# stm32_pi_board.net
KiCad netlist of a schematic drawn in EAGLE
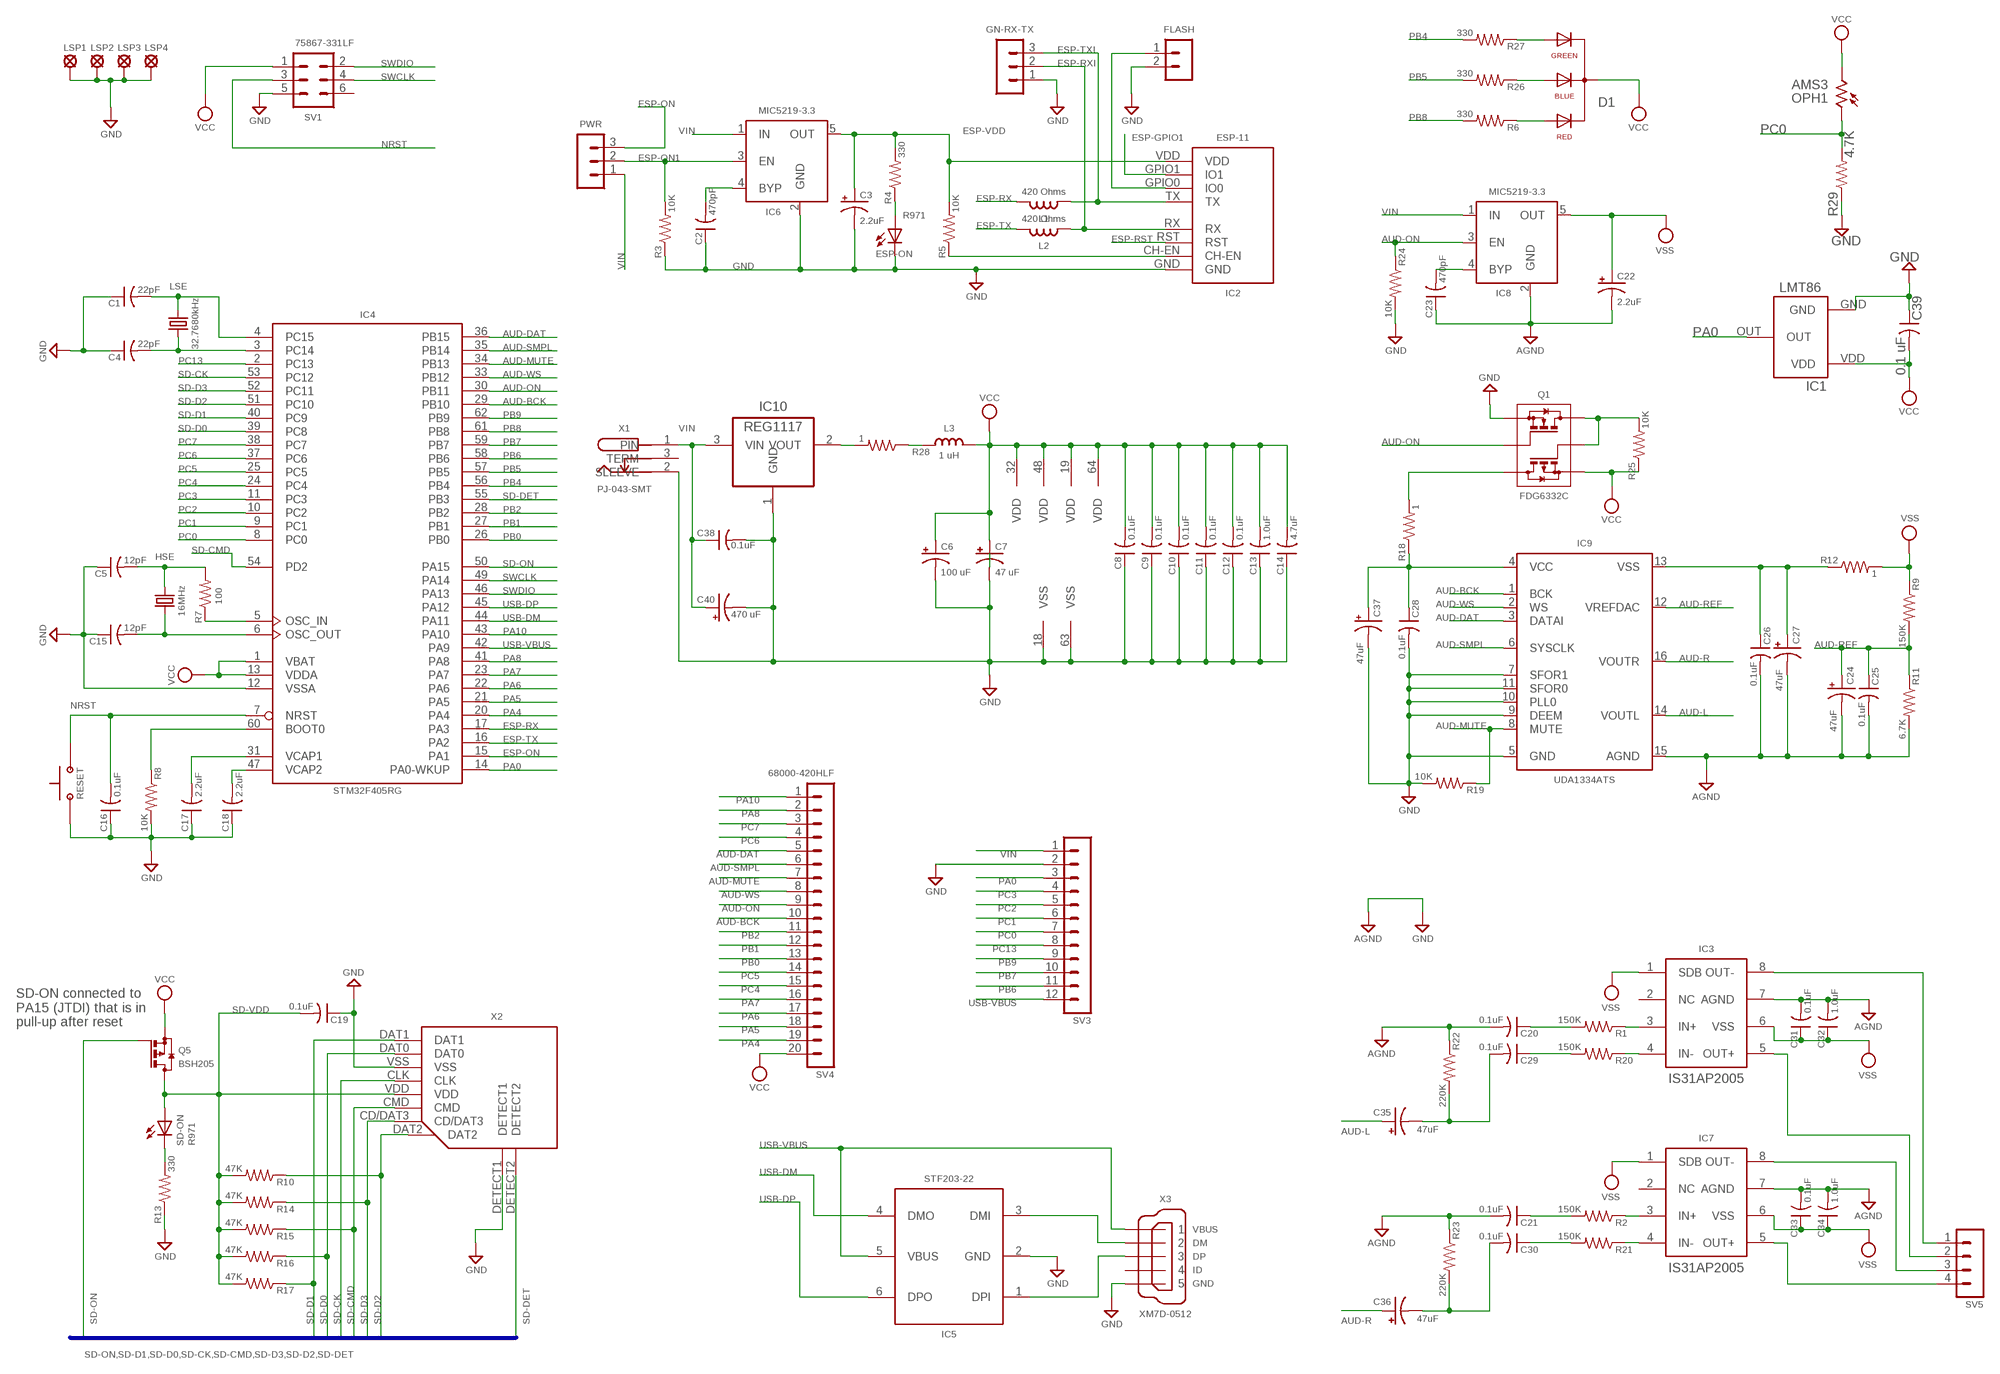
[diagram p0: schematic, sheet 1]

(export (version "E")
  (design (tool "Eeschema 10.0.6"))
  (components
    (comp (ref "C1")
      (value "22pF")
      (footprint "eagle-import:C0805")
      (libsource (lib "eagle-import") (part "C-US0805"))
    )
    (comp (ref "C2")
      (value "470pF")
      (footprint "eagle-import:C0805")
      (libsource (lib "eagle-import") (part "C-US0805"))
    )
    (comp (ref "C3")
      (value "2.2uF")
      (footprint "eagle-import:CPOL0805")
      (libsource (lib "eagle-import") (part "CPOL-US0805"))
    )
    (comp (ref "C4")
      (value "22pF")
      (footprint "eagle-import:C0805")
      (libsource (lib "eagle-import") (part "C-US0805"))
    )
    (comp (ref "C5")
      (value "12pF")
      (footprint "eagle-import:C0805")
      (libsource (lib "eagle-import") (part "C-US0805"))
    )
    (comp (ref "C6")
      (value "100 uF")
      (footprint "eagle-import:CPOL1311")
      (libsource (lib "eagle-import") (part "CPOL-US1311"))
    )
    (comp (ref "C7")
      (value "47 uF")
      (footprint "eagle-import:CPOL0805")
      (libsource (lib "eagle-import") (part "CPOL-US0805"))
    )
    (comp (ref "C8")
      (value "0.1uF")
      (footprint "eagle-import:C0805")
      (libsource (lib "eagle-import") (part "C-US0805"))
    )
    (comp (ref "C9")
      (value "0.1uF")
      (footprint "eagle-import:C0805")
      (libsource (lib "eagle-import") (part "C-US0805"))
    )
    (comp (ref "C10")
      (value "0.1uF")
      (footprint "eagle-import:C0805")
      (libsource (lib "eagle-import") (part "C-US0805"))
    )
    (comp (ref "C11")
      (value "0.1uF")
      (footprint "eagle-import:C0805")
      (libsource (lib "eagle-import") (part "C-US0805"))
    )
    (comp (ref "C12")
      (value "0.1uF")
      (footprint "eagle-import:C0805")
      (libsource (lib "eagle-import") (part "C-US0805"))
    )
    (comp (ref "C13")
      (value "1.0uF")
      (footprint "eagle-import:C0805")
      (libsource (lib "eagle-import") (part "C-US0805"))
    )
    (comp (ref "C14")
      (value "4.7uF")
      (footprint "eagle-import:C0805")
      (libsource (lib "eagle-import") (part "C-US0805"))
    )
    (comp (ref "C15")
      (value "12pF")
      (footprint "eagle-import:C0805")
      (libsource (lib "eagle-import") (part "C-US0805"))
    )
    (comp (ref "C16")
      (value "0.1uF")
      (footprint "eagle-import:C0805")
      (libsource (lib "eagle-import") (part "C-US0805"))
    )
    (comp (ref "C17")
      (value "2.2uF")
      (footprint "eagle-import:C0805")
      (libsource (lib "eagle-import") (part "C-US0805"))
    )
    (comp (ref "C18")
      (value "2.2uF")
      (footprint "eagle-import:C0805")
      (libsource (lib "eagle-import") (part "C-US0805"))
    )
    (comp (ref "C19")
      (value "0.1uF")
      (footprint "eagle-import:C0805")
      (libsource (lib "eagle-import") (part "C-US0805"))
    )
    (comp (ref "C20")
      (value "0.1uF")
      (footprint "eagle-import:C0805")
      (libsource (lib "eagle-import") (part "C-US0805"))
    )
    (comp (ref "C21")
      (value "0.1uF")
      (footprint "eagle-import:C0805")
      (libsource (lib "eagle-import") (part "C-US0805"))
    )
    (comp (ref "C22")
      (value "2.2uF")
      (footprint "eagle-import:CPOL0805")
      (libsource (lib "eagle-import") (part "CPOL-US0805"))
    )
    (comp (ref "C23")
      (value "470pF")
      (footprint "eagle-import:C0805")
      (libsource (lib "eagle-import") (part "C-US0805"))
    )
    (comp (ref "C24")
      (value "47uF")
      (footprint "eagle-import:CPOL1311")
      (libsource (lib "eagle-import") (part "CPOL-US1311"))
    )
    (comp (ref "C25")
      (value "0.1uF")
      (footprint "eagle-import:C0805")
      (libsource (lib "eagle-import") (part "C-US0805"))
    )
    (comp (ref "C26")
      (value "0.1uF")
      (footprint "eagle-import:C0805")
      (libsource (lib "eagle-import") (part "C-US0805"))
    )
    (comp (ref "C27")
      (value "47uF")
      (footprint "eagle-import:CPOL1311")
      (libsource (lib "eagle-import") (part "CPOL-US1311"))
    )
    (comp (ref "C28")
      (value "0.1uF")
      (footprint "eagle-import:C0805")
      (libsource (lib "eagle-import") (part "C-US0805"))
    )
    (comp (ref "C29")
      (value "0.1uF")
      (footprint "eagle-import:C0805")
      (libsource (lib "eagle-import") (part "C-US0805"))
    )
    (comp (ref "C30")
      (value "0.1uF")
      (footprint "eagle-import:C0805")
      (libsource (lib "eagle-import") (part "C-US0805"))
    )
    (comp (ref "C31")
      (value "0.1uF")
      (footprint "eagle-import:C0805")
      (libsource (lib "eagle-import") (part "C-US0805"))
    )
    (comp (ref "C32")
      (value "1.0uF")
      (footprint "eagle-import:C0805")
      (libsource (lib "eagle-import") (part "C-US0805"))
    )
    (comp (ref "C33")
      (value "0.1uF")
      (footprint "eagle-import:C0805")
      (libsource (lib "eagle-import") (part "C-US0805"))
    )
    (comp (ref "C34")
      (value "1.0uF")
      (footprint "eagle-import:C0805")
      (libsource (lib "eagle-import") (part "C-US0805"))
    )
    (comp (ref "C35")
      (value "47uF")
      (footprint "eagle-import:CPOL1311")
      (libsource (lib "eagle-import") (part "CPOL-US1311"))
    )
    (comp (ref "C36")
      (value "47uF")
      (footprint "eagle-import:CPOL1311")
      (libsource (lib "eagle-import") (part "CPOL-US1311"))
    )
    (comp (ref "C37")
      (value "47uF")
      (footprint "eagle-import:CPOL1311")
      (libsource (lib "eagle-import") (part "CPOL-US1311"))
    )
    (comp (ref "C38")
      (value "0.1uF")
      (footprint "eagle-import:C0805")
      (libsource (lib "eagle-import") (part "C-US0805"))
    )
    (comp (ref "C39")
      (value "0.1 uF")
      (footprint "eagle-import:C0805")
      (libsource (lib "eagle-import") (part "C-US0805"))
    )
    (comp (ref "C40")
      (value "470 uF")
      (footprint "eagle-import:CPOL2917")
      (libsource (lib "eagle-import") (part "CPOL-US2917"))
    )
    (comp (ref "D1")
      (value "RGB-LED3X1MM")
      (footprint "eagle-import:RGB-LED-SMD-3X1")
      (libsource (lib "eagle-import") (part "RGB-LED3X1MM"))
    )
    (comp (ref "ESP-ON")
      (value "R971")
      (footprint "eagle-import:CHIP-LED0805")
      (libsource (lib "eagle-import") (part "LEDCHIP-LED0805"))
    )
    (comp (ref "FLASH")
      (value "MA02-1")
      (footprint "eagle-import:MA02-1")
      (libsource (lib "eagle-import") (part "MA02-1"))
    )
    (comp (ref "GN-RX-TX")
      (value "MA03-1PL")
      (footprint "eagle-import:MA03-1")
      (libsource (lib "eagle-import") (part "MA03-1PL"))
    )
    (comp (ref "HSE")
      (value "16MHz")
      (footprint "eagle-import:Q-HC-46X")
      (libsource (lib "eagle-import") (part "Q-HSEHC-46X"))
    )
    (comp (ref "IC1")
      (value "LMT86")
      (footprint "eagle-import:LMT86")
      (libsource (lib "eagle-import") (part "LMT86"))
    )
    (comp (ref "IC2")
      (value "ESP-11")
      (footprint "eagle-import:ESP-11")
      (libsource (lib "eagle-import") (part "ESP-11"))
    )
    (comp (ref "IC3")
      (value "IS31AP2005")
      (footprint "eagle-import:MSOP-8")
      (libsource (lib "eagle-import") (part "IS31AP2005"))
    )
    (comp (ref "IC4")
      (value "STM32F405RG")
      (footprint "eagle-import:LQFP64")
      (libsource (lib "eagle-import") (part "STM32F405RTG"))
    )
    (comp (ref "IC5")
      (value "STF203-22")
      (footprint "eagle-import:SC70-6")
      (libsource (lib "eagle-import") (part "STF203-22"))
    )
    (comp (ref "IC6")
      (value "MIC5219-3.3")
      (footprint "eagle-import:SOT23-5")
      (libsource (lib "eagle-import") (part "MIC5219XX"))
    )
    (comp (ref "IC7")
      (value "IS31AP2005")
      (footprint "eagle-import:MSOP-8")
      (libsource (lib "eagle-import") (part "IS31AP2005"))
    )
    (comp (ref "IC8")
      (value "MIC5219-3.3")
      (footprint "eagle-import:SOT23-5")
      (libsource (lib "eagle-import") (part "MIC5219XX"))
    )
    (comp (ref "IC9")
      (value "UDA1334ATS")
      (footprint "eagle-import:SSOP16")
      (libsource (lib "eagle-import") (part "UDA1334ATS"))
    )
    (comp (ref "IC10")
      (value "REG1117")
      (footprint "eagle-import:SOT223")
      (libsource (lib "eagle-import") (part "REG1117"))
    )
    (comp (ref "L1")
      (value "420 Ohms")
      (footprint "eagle-import:L0603")
      (libsource (lib "eagle-import") (part "L-USL0603"))
    )
    (comp (ref "L2")
      (value "420 Ohms")
      (footprint "eagle-import:L0603")
      (libsource (lib "eagle-import") (part "L-USL0603"))
    )
    (comp (ref "L3")
      (value "1 uH")
      (footprint "eagle-import:L0805")
      (libsource (lib "eagle-import") (part "L-USL0805"))
    )
    (comp (ref "LSE")
      (value "32.7680kHz")
      (footprint "eagle-import:Q-CM7V-T1A")
      (libsource (lib "eagle-import") (part "Q-LSECM7V-T1A"))
    )
    (comp (ref "LSP1")
      (value "LSP27")
      (footprint "eagle-import:LSP27")
      (libsource (lib "eagle-import") (part "LSP27"))
    )
    (comp (ref "LSP2")
      (value "LSP27")
      (footprint "eagle-import:LSP27")
      (libsource (lib "eagle-import") (part "LSP27"))
    )
    (comp (ref "LSP3")
      (value "LSP27")
      (footprint "eagle-import:LSP27")
      (libsource (lib "eagle-import") (part "LSP27"))
    )
    (comp (ref "LSP4")
      (value "LSP27")
      (footprint "eagle-import:LSP27")
      (libsource (lib "eagle-import") (part "LSP27"))
    )
    (comp (ref "OPH1")
      (value "AMS3")
      (footprint "eagle-import:VT900")
      (libsource (lib "eagle-import") (part "VT935GB"))
    )
    (comp (ref "PWR")
      (value "MA03-1PL")
      (footprint "eagle-import:MA03-1")
      (libsource (lib "eagle-import") (part "MA03-1PL"))
    )
    (comp (ref "Q1")
      (value "FDG6332C")
      (footprint "eagle-import:SC70-6")
      (libsource (lib "eagle-import") (part "N-P-MOS"))
    )
    (comp (ref "Q5")
      (value "BSH205")
      (footprint "eagle-import:SOT23")
      (libsource (lib "eagle-import") (part "BSH205G2R"))
    )
    (comp (ref "R1")
      (value "150K")
      (footprint "eagle-import:R0805")
      (libsource (lib "eagle-import") (part "R-US0805"))
    )
    (comp (ref "R2")
      (value "150K")
      (footprint "eagle-import:R0805")
      (libsource (lib "eagle-import") (part "R-US0805"))
    )
    (comp (ref "R3")
      (value "10K")
      (footprint "eagle-import:R0805")
      (libsource (lib "eagle-import") (part "R-US0805"))
    )
    (comp (ref "R4")
      (value "330")
      (footprint "eagle-import:R0805")
      (libsource (lib "eagle-import") (part "R-US0805"))
    )
    (comp (ref "R5")
      (value "10K")
      (footprint "eagle-import:R0805")
      (libsource (lib "eagle-import") (part "R-US0805"))
    )
    (comp (ref "R6")
      (value "330")
      (footprint "eagle-import:R0805")
      (libsource (lib "eagle-import") (part "R-US0805"))
    )
    (comp (ref "R7")
      (value "100")
      (footprint "eagle-import:R0805")
      (libsource (lib "eagle-import") (part "R-US0805"))
    )
    (comp (ref "R8")
      (value "10K")
      (footprint "eagle-import:R0805")
      (libsource (lib "eagle-import") (part "R-US0805"))
    )
    (comp (ref "R9")
      (value "150K")
      (footprint "eagle-import:R0805")
      (libsource (lib "eagle-import") (part "R-US0805"))
    )
    (comp (ref "R10")
      (value "47K")
      (footprint "eagle-import:R0805")
      (libsource (lib "eagle-import") (part "R-US0805"))
    )
    (comp (ref "R11")
      (value "6.7K")
      (footprint "eagle-import:R0805")
      (libsource (lib "eagle-import") (part "R-US0805"))
    )
    (comp (ref "R12")
      (value "1")
      (footprint "eagle-import:R0805")
      (libsource (lib "eagle-import") (part "R-US0805"))
    )
    (comp (ref "R13")
      (value "330")
      (footprint "eagle-import:R0805")
      (libsource (lib "eagle-import") (part "R-US0805"))
    )
    (comp (ref "R14")
      (value "47K")
      (footprint "eagle-import:R0805")
      (libsource (lib "eagle-import") (part "R-US0805"))
    )
    (comp (ref "R15")
      (value "47K")
      (footprint "eagle-import:R0805")
      (libsource (lib "eagle-import") (part "R-US0805"))
    )
    (comp (ref "R16")
      (value "47K")
      (footprint "eagle-import:R0805")
      (libsource (lib "eagle-import") (part "R-US0805"))
    )
    (comp (ref "R17")
      (value "47K")
      (footprint "eagle-import:R0805")
      (libsource (lib "eagle-import") (part "R-US0805"))
    )
    (comp (ref "R18")
      (value "1")
      (footprint "eagle-import:R0805")
      (libsource (lib "eagle-import") (part "R-US0805"))
    )
    (comp (ref "R19")
      (value "10K")
      (footprint "eagle-import:R0805")
      (libsource (lib "eagle-import") (part "R-US0805"))
    )
    (comp (ref "R20")
      (value "150K")
      (footprint "eagle-import:R0805")
      (libsource (lib "eagle-import") (part "R-US0805"))
    )
    (comp (ref "R21")
      (value "150K")
      (footprint "eagle-import:R0805")
      (libsource (lib "eagle-import") (part "R-US0805"))
    )
    (comp (ref "R22")
      (value "220K")
      (footprint "eagle-import:R0805")
      (libsource (lib "eagle-import") (part "R-US0805"))
    )
    (comp (ref "R23")
      (value "220K")
      (footprint "eagle-import:R0805")
      (libsource (lib "eagle-import") (part "R-US0805"))
    )
    (comp (ref "R24")
      (value "10K")
      (footprint "eagle-import:R0805")
      (libsource (lib "eagle-import") (part "R-US0805"))
    )
    (comp (ref "R25")
      (value "10K")
      (footprint "eagle-import:R0805")
      (libsource (lib "eagle-import") (part "R-US0805"))
    )
    (comp (ref "R26")
      (value "330")
      (footprint "eagle-import:R0805")
      (libsource (lib "eagle-import") (part "R-US0805"))
    )
    (comp (ref "R27")
      (value "330")
      (footprint "eagle-import:R0805")
      (libsource (lib "eagle-import") (part "R-US0805"))
    )
    (comp (ref "R28")
      (value "1")
      (footprint "eagle-import:R0805")
      (libsource (lib "eagle-import") (part "R-US0805"))
    )
    (comp (ref "R29")
      (value "4.7K")
      (footprint "eagle-import:R0805")
      (libsource (lib "eagle-import") (part "R-US0805"))
    )
    (comp (ref "RESET")
      (value "BUTTON-FSM14JRT")
      (footprint "eagle-import:BUTTON-FSM14JRT")
      (libsource (lib "eagle-import") (part "BUTTON-FSM14JRT"))
    )
    (comp (ref "SD-ON")
      (value "R971")
      (footprint "eagle-import:CHIP-LED0805")
      (libsource (lib "eagle-import") (part "LEDCHIP-LED0805"))
    )
    (comp (ref "SV1")
      (value "75867-331LF")
      (footprint "eagle-import:MA03-2")
      (libsource (lib "eagle-import") (part "MA03-2"))
    )
    (comp (ref "SV3")
      (value "MA12-1NO-PL")
      (footprint "eagle-import:MA12-1-NO-PL")
      (libsource (lib "eagle-import") (part "MA12-1NO-PL"))
    )
    (comp (ref "SV4")
      (value "68000-420HLF")
      (footprint "eagle-import:MA20-1-NO-PL")
      (libsource (lib "eagle-import") (part "MA20-1NO-PL"))
    )
    (comp (ref "SV5")
      (value "MA04-1PL")
      (footprint "eagle-import:MA04-1")
      (libsource (lib "eagle-import") (part "MA04-1PL"))
    )
    (comp (ref "X1")
      (value "PJ-043-SMT")
      (footprint "eagle-import:BUCHSE-1.0X3.2")
      (libsource (lib "eagle-import") (part "DC-POWER-JACK2"))
    )
    (comp (ref "X2")
      (value "DM3AT")
      (footprint "eagle-import:DM3AT")
      (libsource (lib "eagle-import") (part "MICRO-SD-DM3AT"))
    )
    (comp (ref "X3")
      (value "XM7D-0512")
      (footprint "eagle-import:XM7D-0512")
      (libsource (lib "eagle-import") (part "MINI-USB-5-DPI"))
    )
  )
  (nets
    (net (code "1") (name "/AUD-BCK") (class "Default")
      (node (ref "IC4") (pin "29") (pinfunction "PB10_29") (pintype "bidirectional"))
      (node (ref "IC9") (pin "1") (pinfunction "BCK_1") (pintype "input"))
      (node (ref "SV4") (pin "10") (pinfunction "10_10") (pintype "passive"))
    )
    (net (code "2") (name "/AUD-DAT") (class "Default")
      (node (ref "IC4") (pin "36") (pinfunction "PB15_36") (pintype "bidirectional"))
      (node (ref "IC9") (pin "3") (pinfunction "DATAI_3") (pintype "input"))
      (node (ref "SV4") (pin "5") (pinfunction "5_5") (pintype "passive"))
    )
    (net (code "3") (name "/AUD-L") (class "Default")
      (node (ref "C35") (pin "1+") (pinfunction "+_1+") (pintype "passive"))
      (node (ref "IC9") (pin "14") (pinfunction "VOUTL_14") (pintype "output"))
    )
    (net (code "4") (name "/AUD-MUTE") (class "Default")
      (node (ref "IC4") (pin "34") (pinfunction "PB13_34") (pintype "bidirectional"))
      (node (ref "IC9") (pin "8") (pinfunction "MUTE_8") (pintype "input"))
      (node (ref "R19") (pin "1") (pinfunction "1_1") (pintype "passive"))
      (node (ref "SV4") (pin "7") (pinfunction "7_7") (pintype "passive"))
    )
    (net (code "5") (name "/AUD-ON") (class "Default")
      (node (ref "IC4") (pin "30") (pinfunction "PB11_30") (pintype "bidirectional"))
      (node (ref "IC8") (pin "3") (pinfunction "EN_3") (pintype "input"))
      (node (ref "Q1") (pin "2") (pinfunction "2_2") (pintype "passive"))
      (node (ref "R24") (pin "1") (pinfunction "1_1") (pintype "passive"))
      (node (ref "SV4") (pin "9") (pinfunction "9_9") (pintype "passive"))
    )
    (net (code "6") (name "/AUD-R") (class "Default")
      (node (ref "C36") (pin "1+") (pinfunction "+_1+") (pintype "passive"))
      (node (ref "IC9") (pin "16") (pinfunction "VOUTR_16") (pintype "output"))
    )
    (net (code "7") (name "/AUD-REF") (class "Default")
      (node (ref "C24") (pin "1+") (pinfunction "+_1+") (pintype "passive"))
      (node (ref "C25") (pin "1") (pinfunction "1_1") (pintype "passive"))
      (node (ref "IC9") (pin "12") (pinfunction "VREFDAC_12") (pintype "input"))
      (node (ref "R11") (pin "1") (pinfunction "1_1") (pintype "passive"))
      (node (ref "R9") (pin "2") (pinfunction "2_2") (pintype "passive"))
    )
    (net (code "8") (name "/AUD-SMPL") (class "Default")
      (node (ref "IC4") (pin "35") (pinfunction "PB14_35") (pintype "bidirectional"))
      (node (ref "IC9") (pin "6") (pinfunction "SYSCLK_6") (pintype "input"))
      (node (ref "SV4") (pin "6") (pinfunction "6_6") (pintype "passive"))
    )
    (net (code "9") (name "/AUD-WS") (class "Default")
      (node (ref "IC4") (pin "33") (pinfunction "PB12_33") (pintype "bidirectional"))
      (node (ref "IC9") (pin "2") (pinfunction "WS_2") (pintype "input"))
      (node (ref "SV4") (pin "8") (pinfunction "8_8") (pintype "passive"))
    )
    (net (code "10") (name "/ESP-GPIO1") (class "Default")
      (node (ref "IC2") (pin "GPIO1") (pinfunction "IO1_GPIO1") (pintype "bidirectional"))
    )
    (net (code "11") (name "/ESP-ON") (class "Default")
      (node (ref "IC4") (pin "15") (pinfunction "PA1_15") (pintype "bidirectional"))
      (node (ref "PWR") (pin "3") (pinfunction "3_3") (pintype "passive"))
    )
    (net (code "12") (name "/ESP-ON1") (class "Default")
      (node (ref "IC6") (pin "3") (pinfunction "EN_3") (pintype "input"))
      (node (ref "PWR") (pin "2") (pinfunction "2_2") (pintype "passive"))
      (node (ref "R3") (pin "2") (pinfunction "2_2") (pintype "passive"))
    )
    (net (code "13") (name "/ESP-RST") (class "Default")
      (node (ref "IC2") (pin "RST") (pinfunction "RST_RST") (pintype "bidirectional"))
    )
    (net (code "14") (name "/ESP-RX") (class "Default")
      (node (ref "IC4") (pin "17") (pinfunction "PA3_17") (pintype "bidirectional"))
      (node (ref "L1") (pin "2") (pinfunction "2_2") (pintype "passive"))
    )
    (net (code "15") (name "/ESP-RXI") (class "Default")
      (node (ref "GN-RX-TX") (pin "2") (pinfunction "2_2") (pintype "passive"))
      (node (ref "IC2") (pin "RX") (pinfunction "RX_RX") (pintype "bidirectional"))
      (node (ref "L2") (pin "1") (pinfunction "1_1") (pintype "passive"))
    )
    (net (code "16") (name "/ESP-TX") (class "Default")
      (node (ref "IC4") (pin "16") (pinfunction "PA2_16") (pintype "bidirectional"))
      (node (ref "L2") (pin "2") (pinfunction "2_2") (pintype "passive"))
    )
    (net (code "17") (name "/ESP-TXI") (class "Default")
      (node (ref "GN-RX-TX") (pin "3") (pinfunction "3_3") (pintype "passive"))
      (node (ref "IC2") (pin "TX") (pinfunction "TX_TX") (pintype "bidirectional"))
      (node (ref "L1") (pin "1") (pinfunction "1_1") (pintype "passive"))
    )
    (net (code "18") (name "/ESP-VDD") (class "Default")
      (node (ref "C3") (pin "1+") (pinfunction "+_1+") (pintype "passive"))
      (node (ref "IC2") (pin "VDD") (pinfunction "VDD_VDD") (pintype "bidirectional"))
      (node (ref "IC6") (pin "5") (pinfunction "OUT_5") (pintype "output"))
      (node (ref "R4") (pin "2") (pinfunction "2_2") (pintype "passive"))
      (node (ref "R5") (pin "2") (pinfunction "2_2") (pintype "passive"))
    )
    (net (code "19") (name "/NRST") (class "Default")
      (node (ref "C16") (pin "2") (pinfunction "2_2") (pintype "passive"))
      (node (ref "IC4") (pin "7") (pinfunction "NRST_7") (pintype "bidirectional"))
      (node (ref "RESET") (pin "P$2") (pinfunction "2_P$2") (pintype "bidirectional"))
      (node (ref "SV1") (pin "3") (pinfunction "3_3") (pintype "passive"))
    )
    (net (code "20") (name "/PA0") (class "Default")
      (node (ref "IC1") (pin "OUT") (pinfunction "OUT_OUT") (pintype "bidirectional"))
      (node (ref "IC4") (pin "14") (pinfunction "PA0-WKUP_14") (pintype "bidirectional"))
      (node (ref "SV3") (pin "3") (pinfunction "3_3") (pintype "passive"))
    )
    (net (code "21") (name "/PA4") (class "Default")
      (node (ref "IC4") (pin "20") (pinfunction "PA4_20") (pintype "bidirectional"))
      (node (ref "SV4") (pin "19") (pinfunction "19_19") (pintype "passive"))
    )
    (net (code "22") (name "/PA5") (class "Default")
      (node (ref "IC4") (pin "21") (pinfunction "PA5_21") (pintype "bidirectional"))
      (node (ref "SV4") (pin "18") (pinfunction "18_18") (pintype "passive"))
    )
    (net (code "23") (name "/PA6") (class "Default")
      (node (ref "IC4") (pin "22") (pinfunction "PA6_22") (pintype "bidirectional"))
      (node (ref "SV4") (pin "17") (pinfunction "17_17") (pintype "passive"))
    )
    (net (code "24") (name "/PA7") (class "Default")
      (node (ref "IC4") (pin "23") (pinfunction "PA7_23") (pintype "bidirectional"))
      (node (ref "SV4") (pin "16") (pinfunction "16_16") (pintype "passive"))
    )
    (net (code "25") (name "/PA8") (class "Default")
      (node (ref "IC4") (pin "41") (pinfunction "PA8_41") (pintype "bidirectional"))
      (node (ref "SV4") (pin "2") (pinfunction "2_2") (pintype "passive"))
    )
    (net (code "26") (name "/PA10") (class "Default")
      (node (ref "IC4") (pin "43") (pinfunction "PA10_43") (pintype "bidirectional"))
      (node (ref "SV4") (pin "1") (pinfunction "1_1") (pintype "passive"))
    )
    (net (code "27") (name "/PB0") (class "Default")
      (node (ref "IC4") (pin "26") (pinfunction "PB0_26") (pintype "bidirectional"))
      (node (ref "SV4") (pin "13") (pinfunction "13_13") (pintype "passive"))
    )
    (net (code "28") (name "/PB1") (class "Default")
      (node (ref "IC4") (pin "27") (pinfunction "PB1_27") (pintype "bidirectional"))
      (node (ref "SV4") (pin "12") (pinfunction "12_12") (pintype "passive"))
    )
    (net (code "29") (name "/PB2") (class "Default")
      (node (ref "IC4") (pin "28") (pinfunction "PB2_28") (pintype "bidirectional"))
      (node (ref "SV4") (pin "11") (pinfunction "11_11") (pintype "passive"))
    )
    (net (code "30") (name "/PB4") (class "Default")
      (node (ref "IC4") (pin "56") (pinfunction "PB4_56") (pintype "bidirectional"))
      (node (ref "R27") (pin "2") (pinfunction "2_2") (pintype "passive"))
    )
    (net (code "31") (name "/PB5") (class "Default")
      (node (ref "IC4") (pin "57") (pinfunction "PB5_57") (pintype "bidirectional"))
      (node (ref "R26") (pin "2") (pinfunction "2_2") (pintype "passive"))
    )
    (net (code "32") (name "/PB6") (class "Default")
      (node (ref "IC4") (pin "58") (pinfunction "PB6_58") (pintype "bidirectional"))
      (node (ref "SV3") (pin "11") (pinfunction "11_11") (pintype "passive"))
    )
    (net (code "33") (name "/PB7") (class "Default")
      (node (ref "IC4") (pin "59") (pinfunction "PB7_59") (pintype "bidirectional"))
      (node (ref "SV3") (pin "10") (pinfunction "10_10") (pintype "passive"))
    )
    (net (code "34") (name "/PB8") (class "Default")
      (node (ref "IC4") (pin "61") (pinfunction "PB8_61") (pintype "bidirectional"))
      (node (ref "R6") (pin "2") (pinfunction "2_2") (pintype "passive"))
    )
    (net (code "35") (name "/PB9") (class "Default")
      (node (ref "IC4") (pin "62") (pinfunction "PB9_62") (pintype "bidirectional"))
      (node (ref "SV3") (pin "9") (pinfunction "9_9") (pintype "passive"))
    )
    (net (code "36") (name "/PC0") (class "Default")
      (node (ref "IC4") (pin "8") (pinfunction "PC0_8") (pintype "bidirectional"))
      (node (ref "OPH1") (pin "1") (pinfunction "1_1") (pintype "passive"))
      (node (ref "R29") (pin "2") (pinfunction "2_2") (pintype "passive"))
      (node (ref "SV3") (pin "7") (pinfunction "7_7") (pintype "passive"))
    )
    (net (code "37") (name "/PC1") (class "Default")
      (node (ref "IC4") (pin "9") (pinfunction "PC1_9") (pintype "bidirectional"))
      (node (ref "SV3") (pin "6") (pinfunction "6_6") (pintype "passive"))
    )
    (net (code "38") (name "/PC2") (class "Default")
      (node (ref "IC4") (pin "10") (pinfunction "PC2_10") (pintype "bidirectional"))
      (node (ref "SV3") (pin "5") (pinfunction "5_5") (pintype "passive"))
    )
    (net (code "39") (name "/PC3") (class "Default")
      (node (ref "IC4") (pin "11") (pinfunction "PC3_11") (pintype "bidirectional"))
      (node (ref "SV3") (pin "4") (pinfunction "4_4") (pintype "passive"))
    )
    (net (code "40") (name "/PC4") (class "Default")
      (node (ref "IC4") (pin "24") (pinfunction "PC4_24") (pintype "bidirectional"))
      (node (ref "SV4") (pin "15") (pinfunction "15_15") (pintype "passive"))
    )
    (net (code "41") (name "/PC5") (class "Default")
      (node (ref "IC4") (pin "25") (pinfunction "PC5_25") (pintype "bidirectional"))
      (node (ref "SV4") (pin "14") (pinfunction "14_14") (pintype "passive"))
    )
    (net (code "42") (name "/PC6") (class "Default")
      (node (ref "IC4") (pin "37") (pinfunction "PC6_37") (pintype "bidirectional"))
      (node (ref "SV4") (pin "4") (pinfunction "4_4") (pintype "passive"))
    )
    (net (code "43") (name "/PC7") (class "Default")
      (node (ref "IC4") (pin "38") (pinfunction "PC7_38") (pintype "bidirectional"))
      (node (ref "SV4") (pin "3") (pinfunction "3_3") (pintype "passive"))
    )
    (net (code "44") (name "/PC13") (class "Default")
      (node (ref "IC4") (pin "2") (pinfunction "PC13_2") (pintype "bidirectional"))
      (node (ref "SV3") (pin "8") (pinfunction "8_8") (pintype "passive"))
    )
    (net (code "45") (name "/SD-CK") (class "Default")
      (node (ref "IC4") (pin "53") (pinfunction "PC12_53") (pintype "bidirectional"))
      (node (ref "X2") (pin "CLK") (pinfunction "CLK_CLK") (pintype "bidirectional"))
    )
    (net (code "46") (name "/SD-CMD") (class "Default")
      (node (ref "IC4") (pin "54") (pinfunction "PD2_54") (pintype "bidirectional"))
      (node (ref "R15") (pin "1") (pinfunction "1_1") (pintype "passive"))
      (node (ref "X2") (pin "CMD") (pinfunction "CMD_CMD") (pintype "bidirectional"))
    )
    (net (code "47") (name "/SD-D0") (class "Default")
      (node (ref "IC4") (pin "39") (pinfunction "PC8_39") (pintype "bidirectional"))
      (node (ref "R16") (pin "1") (pinfunction "1_1") (pintype "passive"))
      (node (ref "X2") (pin "DAT0") (pinfunction "DAT0_DAT0") (pintype "bidirectional"))
    )
    (net (code "48") (name "/SD-D1") (class "Default")
      (node (ref "IC4") (pin "40") (pinfunction "PC9_40") (pintype "bidirectional"))
      (node (ref "R17") (pin "1") (pinfunction "1_1") (pintype "passive"))
      (node (ref "X2") (pin "DAT1") (pinfunction "DAT1_DAT1") (pintype "bidirectional"))
    )
    (net (code "49") (name "/SD-D2") (class "Default")
      (node (ref "IC4") (pin "51") (pinfunction "PC10_51") (pintype "bidirectional"))
      (node (ref "R10") (pin "1") (pinfunction "1_1") (pintype "passive"))
      (node (ref "X2") (pin "DAT2") (pinfunction "DAT2_DAT2") (pintype "bidirectional"))
    )
    (net (code "50") (name "/SD-D3") (class "Default")
      (node (ref "IC4") (pin "52") (pinfunction "PC11_52") (pintype "bidirectional"))
      (node (ref "R14") (pin "1") (pinfunction "1_1") (pintype "passive"))
      (node (ref "X2") (pin "CD/DAT3") (pinfunction "CD/DAT3_CD/DAT3") (pintype "bidirectional"))
    )
    (net (code "51") (name "/SD-DET") (class "Default")
      (node (ref "IC4") (pin "55") (pinfunction "PB3_55") (pintype "bidirectional"))
      (node (ref "X2") (pin "DETECT2") (pinfunction "DETECT2_DETECT2") (pintype "bidirectional"))
    )
    (net (code "52") (name "/SD-ON") (class "Default")
      (node (ref "IC4") (pin "50") (pinfunction "PA15_50") (pintype "bidirectional"))
      (node (ref "Q5") (pin "1") (pinfunction "G_1") (pintype "passive"))
    )
    (net (code "53") (name "/SD-VDD") (class "Default")
      (node (ref "C19") (pin "2") (pinfunction "2_2") (pintype "passive"))
      (node (ref "Q5") (pin "3") (pinfunction "D_3") (pintype "passive"))
      (node (ref "R10") (pin "2") (pinfunction "2_2") (pintype "passive"))
      (node (ref "R14") (pin "2") (pinfunction "2_2") (pintype "passive"))
      (node (ref "R15") (pin "2") (pinfunction "2_2") (pintype "passive"))
      (node (ref "R16") (pin "2") (pinfunction "2_2") (pintype "passive"))
      (node (ref "R17") (pin "2") (pinfunction "2_2") (pintype "passive"))
      (node (ref "SD-ON") (pin "A") (pinfunction "A_A") (pintype "passive"))
      (node (ref "X2") (pin "VDD") (pinfunction "VDD_VDD") (pintype "power_in"))
    )
    (net (code "54") (name "/SWCLK") (class "Default")
      (node (ref "IC4") (pin "49") (pinfunction "PA14_49") (pintype "bidirectional"))
      (node (ref "SV1") (pin "4") (pinfunction "4_4") (pintype "passive"))
    )
    (net (code "55") (name "/SWDIO") (class "Default")
      (node (ref "IC4") (pin "46") (pinfunction "PA13_46") (pintype "bidirectional"))
      (node (ref "SV1") (pin "2") (pinfunction "2_2") (pintype "passive"))
    )
    (net (code "56") (name "/USB-DM") (class "Default")
      (node (ref "IC4") (pin "44") (pinfunction "PA11_44") (pintype "bidirectional"))
      (node (ref "IC5") (pin "4") (pinfunction "DMO_4") (pintype "bidirectional"))
    )
    (net (code "57") (name "/USB-DP") (class "Default")
      (node (ref "IC4") (pin "45") (pinfunction "PA12_45") (pintype "bidirectional"))
      (node (ref "IC5") (pin "6") (pinfunction "DPO_6") (pintype "bidirectional"))
    )
    (net (code "58") (name "/USB-VBUS") (class "Default")
      (node (ref "IC4") (pin "42") (pinfunction "PA9_42") (pintype "bidirectional"))
      (node (ref "IC5") (pin "5") (pinfunction "VBUS_5") (pintype "bidirectional"))
      (node (ref "SV3") (pin "12") (pinfunction "12_12") (pintype "passive"))
      (node (ref "X3") (pin "1") (pinfunction "1_1") (pintype "passive"))
    )
    (net (code "59") (name "/VIN") (class "Default")
      (node (ref "C38") (pin "1") (pinfunction "1_1") (pintype "passive"))
      (node (ref "C40") (pin "+") (pinfunction "+_+") (pintype "passive"))
      (node (ref "IC10") (pin "3") (pinfunction "VIN_3") (pintype "input"))
      (node (ref "IC6") (pin "1") (pinfunction "IN_1") (pintype "input"))
      (node (ref "IC8") (pin "1") (pinfunction "IN_1") (pintype "input"))
      (node (ref "PWR") (pin "1") (pinfunction "1_1") (pintype "passive"))
      (node (ref "SV3") (pin "1") (pinfunction "1_1") (pintype "passive"))
      (node (ref "X1") (pin "1") (pinfunction "PIN_1") (pintype "power_in"))
    )
    (net (code "61") (name "AGND") (class "Default")
      (node (ref "C1") (pin "1") (pinfunction "1_1") (pintype "passive"))
      (node (ref "C10") (pin "1") (pinfunction "1_1") (pintype "passive"))
      (node (ref "C11") (pin "1") (pinfunction "1_1") (pintype "passive"))
      (node (ref "C12") (pin "1") (pinfunction "1_1") (pintype "passive"))
      (node (ref "C13") (pin "1") (pinfunction "1_1") (pintype "passive"))
      (node (ref "C14") (pin "1") (pinfunction "1_1") (pintype "passive"))
      (node (ref "C15") (pin "1") (pinfunction "1_1") (pintype "passive"))
      (node (ref "C16") (pin "1") (pinfunction "1_1") (pintype "passive"))
      (node (ref "C17") (pin "1") (pinfunction "1_1") (pintype "passive"))
      (node (ref "C18") (pin "1") (pinfunction "1_1") (pintype "passive"))
      (node (ref "C19") (pin "1") (pinfunction "1_1") (pintype "passive"))
      (node (ref "C2") (pin "1") (pinfunction "1_1") (pintype "passive"))
      (node (ref "C20") (pin "2") (pinfunction "2_2") (pintype "passive"))
      (node (ref "C21") (pin "2") (pinfunction "2_2") (pintype "passive"))
      (node (ref "C22") (pin "2-") (pinfunction "-_2-") (pintype "passive"))
      (node (ref "C23") (pin "1") (pinfunction "1_1") (pintype "passive"))
      (node (ref "C24") (pin "2-") (pinfunction "-_2-") (pintype "passive"))
      (node (ref "C25") (pin "2") (pinfunction "2_2") (pintype "passive"))
      (node (ref "C26") (pin "2") (pinfunction "2_2") (pintype "passive"))
      (node (ref "C27") (pin "2-") (pinfunction "-_2-") (pintype "passive"))
      (node (ref "C28") (pin "2") (pinfunction "2_2") (pintype "passive"))
      (node (ref "C3") (pin "2-") (pinfunction "-_2-") (pintype "passive"))
      (node (ref "C31") (pin "2") (pinfunction "2_2") (pintype "passive"))
      (node (ref "C32") (pin "2") (pinfunction "2_2") (pintype "passive"))
      (node (ref "C33") (pin "2") (pinfunction "2_2") (pintype "passive"))
      (node (ref "C34") (pin "2") (pinfunction "2_2") (pintype "passive"))
      (node (ref "C37") (pin "2-") (pinfunction "-_2-") (pintype "passive"))
      (node (ref "C38") (pin "2") (pinfunction "2_2") (pintype "passive"))
      (node (ref "C39") (pin "1") (pinfunction "1_1") (pintype "passive"))
      (node (ref "C4") (pin "1") (pinfunction "1_1") (pintype "passive"))
      (node (ref "C40") (pin "-") (pinfunction "-_-") (pintype "passive"))
      (node (ref "C5") (pin "1") (pinfunction "1_1") (pintype "passive"))
      (node (ref "C6") (pin "2-") (pinfunction "-_2-") (pintype "passive"))
      (node (ref "C7") (pin "2-") (pinfunction "-_2-") (pintype "passive"))
      (node (ref "C8") (pin "1") (pinfunction "1_1") (pintype "passive"))
      (node (ref "C9") (pin "1") (pinfunction "1_1") (pintype "passive"))
      (node (ref "ESP-ON") (pin "C") (pinfunction "C_C") (pintype "passive"))
      (node (ref "FLASH") (pin "2") (pinfunction "2_2") (pintype "passive"))
      (node (ref "GN-RX-TX") (pin "1") (pinfunction "1_1") (pintype "passive"))
      (node (ref "IC1") (pin "GND") (pinfunction "GND_GND") (pintype "power_in"))
      (node (ref "IC10") (pin "1") (pinfunction "GND_1") (pintype "power_in"))
      (node (ref "IC2") (pin "GND") (pinfunction "GND_GND") (pintype "bidirectional"))
      (node (ref "IC3") (pin "7") (pinfunction "AGND_7") (pintype "bidirectional"))
      (node (ref "IC4") (pin "12") (pinfunction "VSSA_12") (pintype "power_in"))
      (node (ref "IC4") (pin "18") (pinfunction "VSS_18") (pintype "power_in"))
      (node (ref "IC4") (pin "63") (pinfunction "VSS_63") (pintype "power_in"))
      (node (ref "IC5") (pin "2") (pinfunction "GND_2") (pintype "bidirectional"))
      (node (ref "IC6") (pin "2") (pinfunction "GND_2") (pintype "power_in"))
      (node (ref "IC7") (pin "7") (pinfunction "AGND_7") (pintype "bidirectional"))
      (node (ref "IC8") (pin "2") (pinfunction "GND_2") (pintype "power_in"))
      (node (ref "IC9") (pin "10") (pinfunction "PLL0_10") (pintype "input"))
      (node (ref "IC9") (pin "11") (pinfunction "SFOR0_11") (pintype "input"))
      (node (ref "IC9") (pin "15") (pinfunction "AGND_15") (pintype "power_in"))
      (node (ref "IC9") (pin "5") (pinfunction "GND_5") (pintype "power_in"))
      (node (ref "IC9") (pin "7") (pinfunction "SFOR1_7") (pintype "input"))
      (node (ref "IC9") (pin "9") (pinfunction "DEEM_9") (pintype "input"))
      (node (ref "LSP1") (pin "MP") (pinfunction "MP_MP") (pintype "passive"))
      (node (ref "LSP2") (pin "MP") (pinfunction "MP_MP") (pintype "passive"))
      (node (ref "LSP3") (pin "MP") (pinfunction "MP_MP") (pintype "passive"))
      (node (ref "LSP4") (pin "MP") (pinfunction "MP_MP") (pintype "passive"))
      (node (ref "Q1") (pin "1") (pinfunction "1_1") (pintype "passive"))
      (node (ref "R11") (pin "2") (pinfunction "2_2") (pintype "passive"))
      (node (ref "R13") (pin "1") (pinfunction "1_1") (pintype "passive"))
      (node (ref "R19") (pin "2") (pinfunction "2_2") (pintype "passive"))
      (node (ref "R22") (pin "1") (pinfunction "1_1") (pintype "passive"))
      (node (ref "R23") (pin "1") (pinfunction "1_1") (pintype "passive"))
      (node (ref "R24") (pin "2") (pinfunction "2_2") (pintype "passive"))
      (node (ref "R29") (pin "1") (pinfunction "1_1") (pintype "passive"))
      (node (ref "R3") (pin "1") (pinfunction "1_1") (pintype "passive"))
      (node (ref "R8") (pin "2") (pinfunction "2_2") (pintype "passive"))
      (node (ref "RESET") (pin "P$1") (pinfunction "1_P$1") (pintype "bidirectional"))
      (node (ref "SV1") (pin "5") (pinfunction "5_5") (pintype "passive"))
      (node (ref "SV3") (pin "2") (pinfunction "2_2") (pintype "passive"))
      (node (ref "X1") (pin "2") (pinfunction "SLEEVE_2") (pintype "power_in"))
      (node (ref "X2") (pin "DETECT1") (pinfunction "DETECT1_DETECT1") (pintype "bidirectional"))
      (node (ref "X2") (pin "VSS") (pinfunction "VSS_VSS") (pintype "power_in"))
      (node (ref "X3") (pin "5") (pinfunction "5_5") (pintype "passive"))
    )
    (net (code "62") (name "Net-(C5-Pad2)") (class "Default")
      (node (ref "C5") (pin "2") (pinfunction "2_2") (pintype "passive"))
      (node (ref "HSE") (pin "1") (pinfunction "1_1") (pintype "passive"))
      (node (ref "R7") (pin "2") (pinfunction "2_2") (pintype "passive"))
    )
    (net (code "63") (name "Net-(C20-Pad1)") (class "Default")
      (node (ref "C20") (pin "1") (pinfunction "1_1") (pintype "passive"))
      (node (ref "R1") (pin "2") (pinfunction "2_2") (pintype "passive"))
    )
    (net (code "64") (name "Net-(C21-Pad1)") (class "Default")
      (node (ref "C21") (pin "1") (pinfunction "1_1") (pintype "passive"))
      (node (ref "R2") (pin "2") (pinfunction "2_2") (pintype "passive"))
    )
    (net (code "65") (name "Net-(C27-+)") (class "Default")
      (node (ref "C26") (pin "1") (pinfunction "1_1") (pintype "passive"))
      (node (ref "C27") (pin "1+") (pinfunction "+_1+") (pintype "passive"))
      (node (ref "IC9") (pin "13") (pinfunction "VSS_13") (pintype "power_in"))
      (node (ref "R12") (pin "1") (pinfunction "1_1") (pintype "passive"))
    )
    (net (code "66") (name "Net-(C29-Pad1)") (class "Default")
      (node (ref "C29") (pin "1") (pinfunction "1_1") (pintype "passive"))
      (node (ref "R20") (pin "2") (pinfunction "2_2") (pintype "passive"))
    )
    (net (code "67") (name "Net-(C30-Pad1)") (class "Default")
      (node (ref "C30") (pin "1") (pinfunction "1_1") (pintype "passive"))
      (node (ref "R21") (pin "2") (pinfunction "2_2") (pintype "passive"))
    )
    (net (code "68") (name "Net-(C35--)") (class "Default")
      (node (ref "C29") (pin "2") (pinfunction "2_2") (pintype "passive"))
      (node (ref "C35") (pin "2-") (pinfunction "-_2-") (pintype "passive"))
      (node (ref "R22") (pin "2") (pinfunction "2_2") (pintype "passive"))
    )
    (net (code "69") (name "Net-(C36--)") (class "Default")
      (node (ref "C30") (pin "2") (pinfunction "2_2") (pintype "passive"))
      (node (ref "C36") (pin "2-") (pinfunction "-_2-") (pintype "passive"))
      (node (ref "R23") (pin "2") (pinfunction "2_2") (pintype "passive"))
    )
    (net (code "70") (name "Net-(C37-+)") (class "Default")
      (node (ref "C28") (pin "1") (pinfunction "1_1") (pintype "passive"))
      (node (ref "C37") (pin "1+") (pinfunction "+_1+") (pintype "passive"))
      (node (ref "IC9") (pin "4") (pinfunction "VCC_4") (pintype "power_in"))
      (node (ref "R18") (pin "1") (pinfunction "1_1") (pintype "passive"))
    )
    (net (code "71") (name "Net-(D1-AB)") (class "Default")
      (node (ref "D1") (pin "P$4") (pinfunction "AB_P$4") (pintype "passive"))
      (node (ref "R26") (pin "1") (pinfunction "1_1") (pintype "passive"))
    )
    (net (code "72") (name "Net-(D1-AG)") (class "Default")
      (node (ref "D1") (pin "P$3") (pinfunction "AG_P$3") (pintype "passive"))
      (node (ref "R27") (pin "1") (pinfunction "1_1") (pintype "passive"))
    )
    (net (code "73") (name "Net-(D1-AR)") (class "Default")
      (node (ref "D1") (pin "P$1") (pinfunction "AR_P$1") (pintype "passive"))
      (node (ref "R6") (pin "1") (pinfunction "1_1") (pintype "passive"))
    )
    (net (code "74") (name "Net-(ESP-ON-PadA)") (class "Default")
      (node (ref "ESP-ON") (pin "A") (pinfunction "A_A") (pintype "passive"))
      (node (ref "R4") (pin "1") (pinfunction "1_1") (pintype "passive"))
    )
    (net (code "75") (name "Net-(IC2-IO0)") (class "Default")
      (node (ref "FLASH") (pin "1") (pinfunction "1_1") (pintype "passive"))
      (node (ref "IC2") (pin "GPIO0") (pinfunction "IO0_GPIO0") (pintype "bidirectional"))
    )
    (net (code "76") (name "Net-(IC2-PadCH-EN)") (class "Default")
      (node (ref "IC2") (pin "CH-EN") (pinfunction "CH-EN_CH-EN") (pintype "bidirectional"))
      (node (ref "R5") (pin "1") (pinfunction "1_1") (pintype "passive"))
    )
    (net (code "77") (name "Net-(IC3-IN+)") (class "Default")
      (node (ref "IC3") (pin "3") (pinfunction "IN+_3") (pintype "bidirectional"))
      (node (ref "R1") (pin "1") (pinfunction "1_1") (pintype "passive"))
    )
    (net (code "78") (name "Net-(IC3-IN-)") (class "Default")
      (node (ref "IC3") (pin "4") (pinfunction "IN-_4") (pintype "bidirectional"))
      (node (ref "R20") (pin "1") (pinfunction "1_1") (pintype "passive"))
    )
    (net (code "79") (name "Net-(IC3-OUT+)") (class "Default")
      (node (ref "IC3") (pin "5") (pinfunction "OUT+_5") (pintype "bidirectional"))
      (node (ref "SV5") (pin "2") (pinfunction "2_2") (pintype "passive"))
    )
    (net (code "80") (name "Net-(IC3-OUT-)") (class "Default")
      (node (ref "IC3") (pin "8") (pinfunction "OUT-_8") (pintype "bidirectional"))
      (node (ref "SV5") (pin "1") (pinfunction "1_1") (pintype "passive"))
    )
    (net (code "81") (name "Net-(IC4A-BOOT0)") (class "Default")
      (node (ref "IC4") (pin "60") (pinfunction "BOOT0_60") (pintype "input"))
      (node (ref "R8") (pin "1") (pinfunction "1_1") (pintype "passive"))
    )
    (net (code "82") (name "Net-(IC4A-OSC_IN)") (class "Default")
      (node (ref "IC4") (pin "5") (pinfunction "OSC_IN_5") (pintype "bidirectional"))
      (node (ref "R7") (pin "1") (pinfunction "1_1") (pintype "passive"))
    )
    (net (code "83") (name "Net-(IC4A-OSC_OUT)") (class "Default")
      (node (ref "C15") (pin "2") (pinfunction "2_2") (pintype "passive"))
      (node (ref "HSE") (pin "2") (pinfunction "2_2") (pintype "passive"))
      (node (ref "IC4") (pin "6") (pinfunction "OSC_OUT_6") (pintype "bidirectional"))
    )
    (net (code "84") (name "Net-(IC4A-PC14)") (class "Default")
      (node (ref "C4") (pin "2") (pinfunction "2_2") (pintype "passive"))
      (node (ref "IC4") (pin "3") (pinfunction "PC14_3") (pintype "bidirectional"))
      (node (ref "LSE") (pin "1") (pinfunction "1_1") (pintype "passive"))
    )
    (net (code "85") (name "Net-(IC4A-PC15)") (class "Default")
      (node (ref "C1") (pin "2") (pinfunction "2_2") (pintype "passive"))
      (node (ref "IC4") (pin "4") (pinfunction "PC15_4") (pintype "bidirectional"))
      (node (ref "LSE") (pin "2") (pinfunction "2_2") (pintype "passive"))
    )
    (net (code "86") (name "Net-(IC4A-VCAP1)") (class "Default")
      (node (ref "C17") (pin "2") (pinfunction "2_2") (pintype "passive"))
      (node (ref "IC4") (pin "31") (pinfunction "VCAP1_31") (pintype "power_in"))
    )
    (net (code "87") (name "Net-(IC4A-VCAP2)") (class "Default")
      (node (ref "C18") (pin "2") (pinfunction "2_2") (pintype "passive"))
      (node (ref "IC4") (pin "47") (pinfunction "VCAP2_47") (pintype "power_in"))
    )
    (net (code "88") (name "Net-(IC5-DMI)") (class "Default")
      (node (ref "IC5") (pin "3") (pinfunction "DMI_3") (pintype "bidirectional"))
      (node (ref "X3") (pin "2") (pinfunction "2_2") (pintype "passive"))
    )
    (net (code "89") (name "Net-(IC5-DPI)") (class "Default")
      (node (ref "IC5") (pin "1") (pinfunction "DPI_1") (pintype "bidirectional"))
      (node (ref "X3") (pin "3") (pinfunction "3_3") (pintype "passive"))
    )
    (net (code "90") (name "Net-(IC6-BYP)") (class "Default")
      (node (ref "C2") (pin "2") (pinfunction "2_2") (pintype "passive"))
      (node (ref "IC6") (pin "4") (pinfunction "BYP_4") (pintype "passive"))
    )
    (net (code "91") (name "Net-(IC7-IN+)") (class "Default")
      (node (ref "IC7") (pin "3") (pinfunction "IN+_3") (pintype "bidirectional"))
      (node (ref "R2") (pin "1") (pinfunction "1_1") (pintype "passive"))
    )
    (net (code "92") (name "Net-(IC7-IN-)") (class "Default")
      (node (ref "IC7") (pin "4") (pinfunction "IN-_4") (pintype "bidirectional"))
      (node (ref "R21") (pin "1") (pinfunction "1_1") (pintype "passive"))
    )
    (net (code "93") (name "Net-(IC7-OUT+)") (class "Default")
      (node (ref "IC7") (pin "5") (pinfunction "OUT+_5") (pintype "bidirectional"))
      (node (ref "SV5") (pin "4") (pinfunction "4_4") (pintype "passive"))
    )
    (net (code "94") (name "Net-(IC7-OUT-)") (class "Default")
      (node (ref "IC7") (pin "8") (pinfunction "OUT-_8") (pintype "bidirectional"))
      (node (ref "SV5") (pin "3") (pinfunction "3_3") (pintype "passive"))
    )
    (net (code "95") (name "Net-(IC8-BYP)") (class "Default")
      (node (ref "C23") (pin "2") (pinfunction "2_2") (pintype "passive"))
      (node (ref "IC8") (pin "4") (pinfunction "BYP_4") (pintype "passive"))
    )
    (net (code "96") (name "Net-(IC10-VOUT)") (class "Default")
      (node (ref "IC10") (pin "2") (pinfunction "VOUT_2") (pintype "output"))
      (node (ref "R28") (pin "2") (pinfunction "2_2") (pintype "passive"))
    )
    (net (code "97") (name "Net-(L3-Pad1)") (class "Default")
      (node (ref "L3") (pin "1") (pinfunction "1_1") (pintype "passive"))
      (node (ref "R28") (pin "1") (pinfunction "1_1") (pintype "passive"))
    )
    (net (code "98") (name "Net-(Q1-Pad3)") (class "Default")
      (node (ref "Q1") (pin "3") (pinfunction "3_3") (pintype "passive"))
      (node (ref "R18") (pin "2") (pinfunction "2_2") (pintype "passive"))
    )
    (net (code "99") (name "Net-(Q1-Pad5)") (class "Default")
      (node (ref "Q1") (pin "5") (pinfunction "5_5") (pintype "passive"))
      (node (ref "Q1") (pin "6") (pinfunction "6_6") (pintype "passive"))
      (node (ref "R25") (pin "2") (pinfunction "2_2") (pintype "passive"))
    )
    (net (code "100") (name "Net-(R13-Pad2)") (class "Default")
      (node (ref "R13") (pin "2") (pinfunction "2_2") (pintype "passive"))
      (node (ref "SD-ON") (pin "C") (pinfunction "C_C") (pintype "passive"))
    )
    (net (code "101") (name "VCC") (class "Default")
      (node (ref "C10") (pin "2") (pinfunction "2_2") (pintype "passive"))
      (node (ref "C11") (pin "2") (pinfunction "2_2") (pintype "passive"))
      (node (ref "C12") (pin "2") (pinfunction "2_2") (pintype "passive"))
      (node (ref "C13") (pin "2") (pinfunction "2_2") (pintype "passive"))
      (node (ref "C14") (pin "2") (pinfunction "2_2") (pintype "passive"))
      (node (ref "C39") (pin "2") (pinfunction "2_2") (pintype "passive"))
      (node (ref "C6") (pin "1+") (pinfunction "+_1+") (pintype "passive"))
      (node (ref "C7") (pin "1+") (pinfunction "+_1+") (pintype "passive"))
      (node (ref "C8") (pin "2") (pinfunction "2_2") (pintype "passive"))
      (node (ref "C9") (pin "2") (pinfunction "2_2") (pintype "passive"))
      (node (ref "D1") (pin "P$2") (pinfunction "C_P$2") (pintype "passive"))
      (node (ref "IC1") (pin "VDD") (pinfunction "VDD_VDD") (pintype "power_in"))
      (node (ref "IC4") (pin "1") (pinfunction "VBAT_1") (pintype "power_in"))
      (node (ref "IC4") (pin "13") (pinfunction "VDDA_13") (pintype "power_in"))
      (node (ref "IC4") (pin "19") (pinfunction "VDD_19") (pintype "power_in"))
      (node (ref "IC4") (pin "32") (pinfunction "VDD_32") (pintype "power_in"))
      (node (ref "IC4") (pin "48") (pinfunction "VDD_48") (pintype "power_in"))
      (node (ref "IC4") (pin "64") (pinfunction "VDD_64") (pintype "power_in"))
      (node (ref "L3") (pin "2") (pinfunction "2_2") (pintype "passive"))
      (node (ref "OPH1") (pin "2") (pinfunction "2_2") (pintype "passive"))
      (node (ref "Q1") (pin "4") (pinfunction "4_4") (pintype "passive"))
      (node (ref "Q5") (pin "2") (pinfunction "S_2") (pintype "passive"))
      (node (ref "R25") (pin "1") (pinfunction "1_1") (pintype "passive"))
      (node (ref "SV1") (pin "1") (pinfunction "1_1") (pintype "passive"))
      (node (ref "SV4") (pin "20") (pinfunction "20_20") (pintype "passive"))
    )
    (net (code "102") (name "VSS") (class "Default")
      (node (ref "C22") (pin "1+") (pinfunction "+_1+") (pintype "passive"))
      (node (ref "C31") (pin "1") (pinfunction "1_1") (pintype "passive"))
      (node (ref "C32") (pin "1") (pinfunction "1_1") (pintype "passive"))
      (node (ref "C33") (pin "1") (pinfunction "1_1") (pintype "passive"))
      (node (ref "C34") (pin "1") (pinfunction "1_1") (pintype "passive"))
      (node (ref "IC3") (pin "1") (pinfunction "SDB_1") (pintype "bidirectional"))
      (node (ref "IC3") (pin "6") (pinfunction "VSS_6") (pintype "bidirectional"))
      (node (ref "IC7") (pin "1") (pinfunction "SDB_1") (pintype "bidirectional"))
      (node (ref "IC7") (pin "6") (pinfunction "VSS_6") (pintype "bidirectional"))
      (node (ref "IC8") (pin "5") (pinfunction "OUT_5") (pintype "output"))
      (node (ref "R12") (pin "2") (pinfunction "2_2") (pintype "passive"))
      (node (ref "R9") (pin "1") (pinfunction "1_1") (pintype "passive"))
    )
    (net (code "103") (name "unconnected-(IC3-NC-Pad2)") (class "Default")
      (node (ref "IC3") (pin "2") (pinfunction "NC_2") (pintype "bidirectional"))
    )
    (net (code "104") (name "unconnected-(IC7-NC-Pad2)") (class "Default")
      (node (ref "IC7") (pin "2") (pinfunction "NC_2") (pintype "bidirectional"))
    )
    (net (code "105") (name "unconnected-(SV1-Pad6)") (class "Default")
      (node (ref "SV1") (pin "6") (pinfunction "6_6") (pintype "passive"))
    )
    (net (code "106") (name "unconnected-(X1-TERM-Pad3)") (class "Default")
      (node (ref "X1") (pin "3") (pinfunction "TERM_3") (pintype "bidirectional"))
    )
    (net (code "107") (name "unconnected-(X3-Pad4)") (class "Default")
      (node (ref "X3") (pin "4") (pinfunction "4_4") (pintype "passive"))
    )
  )
)
